# H_BRIGDE.net
KiCad netlist of a schematic drawn in Altium Designer
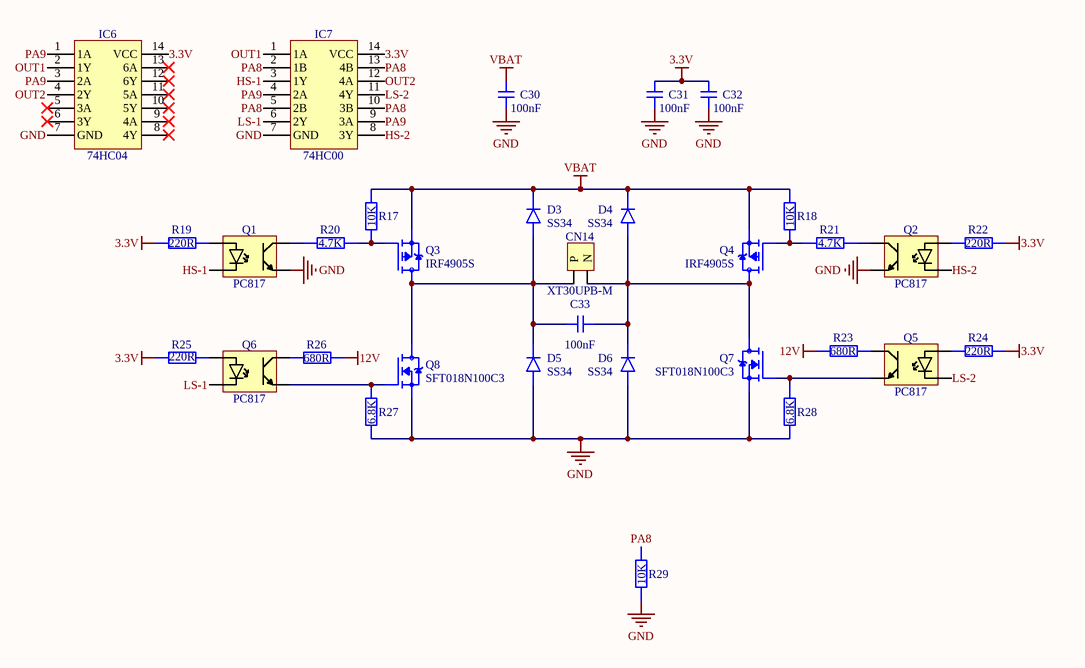
[diagram p0: H_BRIGDE.SchDoc]

(export (version "E")
  (design (tool "Eeschema 10.0.6"))
  (components
    (comp (ref "C30")
      (value "100nF")
      (footprint "CAP-0603-2")
      (description "100nF ±10% 50V Ceramic Capacitor X7R 0603")
      (fields (field (name "MANUFACTURER") "Samsung Electro-Mechanics") (field (name "LCSC PART #") "C1591"))
      (libsource (lib "CbyP") (part "CL10B104KB8NNNC"))
    )
    (comp (ref "C31")
      (value "100nF")
      (footprint "CAP-0603-2")
      (description "100nF ±10% 50V Ceramic Capacitor X7R 0603")
      (fields (field (name "MANUFACTURER") "Samsung Electro-Mechanics") (field (name "LCSC PART #") "C1591"))
      (libsource (lib "CbyP") (part "CL10B104KB8NNNC"))
    )
    (comp (ref "C32")
      (value "100nF")
      (footprint "CAP-0603-2")
      (description "100nF ±10% 50V Ceramic Capacitor X7R 0603")
      (fields (field (name "MANUFACTURER") "Samsung Electro-Mechanics") (field (name "LCSC PART #") "C1591"))
      (libsource (lib "CbyP") (part "CL10B104KB8NNNC"))
    )
    (comp (ref "C33")
      (value "100nF")
      (footprint "CAP-0603-2")
      (description "100nF ±10% 50V Ceramic Capacitor X7R 0603")
      (fields (field (name "MANUFACTURER") "Samsung Electro-Mechanics") (field (name "LCSC PART #") "C1591"))
      (libsource (lib "CbyP") (part "CL10B104KB8NNNC"))
    )
    (comp (ref "CN14")
      (value "XT30UPB-M")
      (footprint "XT30UPB-M")
      (description "Banana and Tip Connector Adapters")
      (fields
        (field (name "MANUFACTURER") "Changzhou Amass Elec")
        (field (name "MFR.PART #") "XT30PW-M30.G.Y")
      )
      (libsource (lib "CbyP") (part "XT30UPB-M"))
    )
    (comp (ref "D3")
      (value "SS34")
      (footprint "SMA(DO-214AC)")
      (description "Diode Independent 40V 3A Surface Mount SMA(DO-214AC)")
      (fields (field (name "MANUFACTURER") "GOODWORK") (field (name "LCSC PART #") "C908680"))
      (libsource (lib "CbyP") (part "SS34"))
    )
    (comp (ref "D4")
      (value "SS34")
      (footprint "SMA(DO-214AC)")
      (description "Diode Independent 40V 3A Surface Mount SMA(DO-214AC)")
      (fields (field (name "MANUFACTURER") "GOODWORK") (field (name "LCSC PART #") "C908680"))
      (libsource (lib "CbyP") (part "SS34"))
    )
    (comp (ref "D5")
      (value "SS34")
      (footprint "SMA(DO-214AC)")
      (description "Diode Independent 40V 3A Surface Mount SMA(DO-214AC)")
      (fields (field (name "MANUFACTURER") "GOODWORK") (field (name "LCSC PART #") "C908680"))
      (libsource (lib "CbyP") (part "SS34"))
    )
    (comp (ref "D6")
      (value "SS34")
      (footprint "SMA(DO-214AC)")
      (description "Diode Independent 40V 3A Surface Mount SMA(DO-214AC)")
      (fields (field (name "MANUFACTURER") "GOODWORK") (field (name "LCSC PART #") "C908680"))
      (libsource (lib "CbyP") (part "SS34"))
    )
    (comp (ref "IC6")
      (value "74HC04")
      (footprint "SOP-14")
      (description "2V~6V 16ns@6V,50pF 2uA 6 1 SOIC-14 Gates and Inverters RoHS")
      (fields (field (name "MANUFACTURER") "TI") (field (name "MFR.PART #") "SN74HC04DR"))
      (libsource (lib "CbyP") (part "SN74HC04DR"))
    )
    (comp (ref "IC7")
      (value "74HC00")
      (footprint "SOP-14")
      (description "2uA 2V~6V 15ns@6V,50pF SOIC-14 Gates and Inverters RoHS")
      (fields (field (name "MANUFACTURER") "TI") (field (name "MFR.PART #") "SN74HC00DR"))
      (libsource (lib "CbyP") (part "SN74HC00DR"))
    )
    (comp (ref "Q1")
      (value "PC817")
      (footprint "SOP-4")
      (description "Phototransistor Output 5kVrms 1 Channel SOP-4-2.54mm")
      (fields (field (name "MANUFACTURER") "UMW") (field (name "MFR.PART #") "PC817C-S"))
      (libsource (lib "CbyP") (part "PC817C-S"))
    )
    (comp (ref "Q2")
      (value "PC817")
      (footprint "SOP-4")
      (description "Phototransistor Output 5kVrms 1 Channel SOP-4-2.54mm")
      (fields (field (name "MANUFACTURER") "UMW") (field (name "MFR.PART #") "PC817C-S"))
      (libsource (lib "") (part "PC817C-S_1"))
    )
    (comp (ref "Q3")
      (value "IRF4905S")
      (footprint "TO-263")
      (description "P-Channel 55V 70A 170W Surface Mount D2PAK")
      (fields (field (name "MANUFACTURER") "Infineon") (field (name "MFR.PART #") "IRF4905STRLPBF"))
      (libsource (lib "CbyP") (part "IRF4905STRLPBF"))
    )
    (comp (ref "Q4")
      (value "IRF4905S")
      (footprint "TO-263")
      (description "P-Channel 55V 70A 170W Surface Mount D2PAK")
      (fields (field (name "MANUFACTURER") "Infineon") (field (name "MFR.PART #") "IRF4905STRLPBF"))
      (libsource (lib "CbyP") (part "IRF4905STRLPBF"))
    )
    (comp (ref "Q5")
      (value "PC817")
      (footprint "SOP-4")
      (description "Phototransistor Output 5kVrms 1 Channel SOP-4-2.54mm")
      (fields (field (name "MANUFACTURER") "UMW") (field (name "MFR.PART #") "PC817C-S"))
      (libsource (lib "") (part "PC817C-S_1"))
    )
    (comp (ref "Q6")
      (value "PC817")
      (footprint "SOP-4")
      (description "Phototransistor Output 5kVrms 1 Channel SOP-4-2.54mm")
      (fields (field (name "MANUFACTURER") "UMW") (field (name "MFR.PART #") "PC817C-S"))
      (libsource (lib "CbyP") (part "PC817C-S"))
    )
    (comp (ref "Q7")
      (value "SFT018N100C3")
      (footprint "TOLL")
      (description "N-Channel 100V 320A 312W Surface Mount TOLL")
      (fields (field (name "MANUFACTURER") "SCILICON") (field (name "LCSC PART #") "C42395330"))
      (libsource (lib "CbyP") (part "SFT018N100C3"))
    )
    (comp (ref "Q8")
      (value "SFT018N100C3")
      (footprint "TOLL")
      (description "N-Channel 100V 320A 312W Surface Mount TOLL")
      (fields (field (name "MANUFACTURER") "SCILICON") (field (name "LCSC PART #") "C42395330"))
      (libsource (lib "CbyP") (part "SFT018N100C3"))
    )
    (comp (ref "R17")
      (value "10K")
      (footprint "RES-0603-1")
      (description "100mW 10kΩ 75V Thick Film Resistor ±100ppm/℃ ±1% 0603 Chip Resistor - Surface Mount RoHS")
      (fields (field (name "MANUFACTURER") "YAGEO") (field (name "LCSC PART #") "C98220"))
      (libsource (lib "CbyP") (part "RC0603FR-0710KL"))
    )
    (comp (ref "R18")
      (value "10K")
      (footprint "RES-0603-1")
      (description "100mW 10kΩ 75V Thick Film Resistor ±100ppm/℃ ±1% 0603 Chip Resistor - Surface Mount RoHS")
      (fields (field (name "MANUFACTURER") "YAGEO") (field (name "LCSC PART #") "C98220"))
      (libsource (lib "CbyP") (part "RC0603FR-0710KL"))
    )
    (comp (ref "R19")
      (value "220R")
      (footprint "RES-0603-1")
      (description "220Ω ±1% 100mW 0603 Thick Film Resistor")
      (fields (field (name "MANUFACTURER") "UNI-ROYAL") (field (name "MFR.PART #") "0603WAF2200T5E"))
      (libsource (lib "CbyP") (part "0603WAF2200T5E"))
    )
    (comp (ref "R20")
      (value "4.7K")
      (footprint "RES-0603-1")
      (description "100mW 4.7kΩ 75V Thick Film Resistor ±100ppm/℃ ±1% 0603 Chip Resistor - Surface Mount RoHS")
      (fields (field (name "MANUFACTURER") "YAGEO") (field (name "MFR.PART #") "RC0603FR-074K7L"))
      (libsource (lib "CbyP") (part "RC0603FR-074K7L"))
    )
    (comp (ref "R21")
      (value "4.7K")
      (footprint "RES-0603-1")
      (description "100mW 4.7kΩ 75V Thick Film Resistor ±100ppm/℃ ±1% 0603 Chip Resistor - Surface Mount RoHS")
      (fields (field (name "MANUFACTURER") "YAGEO") (field (name "MFR.PART #") "RC0603FR-074K7L"))
      (libsource (lib "CbyP") (part "RC0603FR-074K7L"))
    )
    (comp (ref "R22")
      (value "220R")
      (footprint "RES-0603-1")
      (description "220Ω ±1% 100mW 0603 Thick Film Resistor")
      (fields (field (name "MANUFACTURER") "UNI-ROYAL") (field (name "MFR.PART #") "0603WAF2200T5E"))
      (libsource (lib "CbyP") (part "0603WAF2200T5E"))
    )
    (comp (ref "R23")
      (value "680R")
      (footprint "RES-0603-1")
      (description "680Ω ±1% 100mW 0603 Thick Film Resistor")
      (fields (field (name "MANUFACTURER") "FOJAN") (field (name "MFR.PART #") "FRC0603F6800TS"))
      (libsource (lib "CbyP") (part "FRC0603F6800TS"))
    )
    (comp (ref "R24")
      (value "220R")
      (footprint "RES-0603-1")
      (description "220Ω ±1% 100mW 0603 Thick Film Resistor")
      (fields (field (name "MANUFACTURER") "UNI-ROYAL") (field (name "MFR.PART #") "0603WAF2200T5E"))
      (libsource (lib "CbyP") (part "0603WAF2200T5E"))
    )
    (comp (ref "R25")
      (value "220R")
      (footprint "RES-0603-1")
      (description "220Ω ±1% 100mW 0603 Thick Film Resistor")
      (fields (field (name "MANUFACTURER") "UNI-ROYAL") (field (name "MFR.PART #") "0603WAF2200T5E"))
      (libsource (lib "CbyP") (part "0603WAF2200T5E"))
    )
    (comp (ref "R26")
      (value "680R")
      (footprint "RES-0603-1")
      (description "680Ω ±1% 100mW 0603 Thick Film Resistor")
      (fields (field (name "MANUFACTURER") "FOJAN") (field (name "MFR.PART #") "FRC0603F6800TS"))
      (libsource (lib "CbyP") (part "FRC0603F6800TS"))
    )
    (comp (ref "R27")
      (value "6.8K")
      (footprint "RES-0603-1")
      (description "6.8kΩ ±1% 100mW 0603 Thick Film Resistor")
      (fields (field (name "MANUFACTURER") "UNI-ROYAL") (field (name "MFR.PART #") "0603WAF6801T5E"))
      (libsource (lib "CbyP") (part "0603WAF6801T5E"))
    )
    (comp (ref "R28")
      (value "6.8K")
      (footprint "RES-0603-1")
      (description "6.8kΩ ±1% 100mW 0603 Thick Film Resistor")
      (fields (field (name "MANUFACTURER") "UNI-ROYAL") (field (name "MFR.PART #") "0603WAF6801T5E"))
      (libsource (lib "CbyP") (part "0603WAF6801T5E"))
    )
    (comp (ref "R29")
      (value "10K")
      (footprint "RES-0603-1")
      (description "100mW 10kΩ 75V Thick Film Resistor ±100ppm/℃ ±1% 0603 Chip Resistor - Surface Mount RoHS")
      (fields (field (name "MANUFACTURER") "YAGEO") (field (name "LCSC PART #") "C98220"))
      (libsource (lib "CbyP") (part "RC0603FR-0710KL"))
    )
  )
  (nets
    (net (code "1") (name "/HS-1") (class "Default")
      (node (ref "IC7") (pin "3") (pinfunction "1Y_3") (pintype "passive"))
      (node (ref "Q1") (pin "2") (pinfunction "K_2") (pintype "passive"))
    )
    (net (code "2") (name "/HS-2") (class "Default")
      (node (ref "IC7") (pin "8") (pinfunction "3Y_8") (pintype "passive"))
      (node (ref "Q2") (pin "2") (pinfunction "K_2") (pintype "passive"))
    )
    (net (code "3") (name "/LS-1") (class "Default")
      (node (ref "IC7") (pin "6") (pinfunction "2Y_6") (pintype "passive"))
      (node (ref "Q6") (pin "2") (pinfunction "K_2") (pintype "passive"))
    )
    (net (code "4") (name "/LS-2") (class "Default")
      (node (ref "IC7") (pin "11") (pinfunction "4Y_11") (pintype "passive"))
      (node (ref "Q5") (pin "2") (pinfunction "K_2") (pintype "passive"))
    )
    (net (code "5") (name "/OUT1") (class "Default")
      (node (ref "IC6") (pin "2") (pinfunction "1Y_2") (pintype "passive"))
      (node (ref "IC7") (pin "1") (pinfunction "1A_1") (pintype "passive"))
    )
    (net (code "6") (name "/OUT2") (class "Default")
      (node (ref "IC6") (pin "4") (pinfunction "2Y_4") (pintype "passive"))
      (node (ref "IC7") (pin "12") (pinfunction "4A_12") (pintype "passive"))
    )
    (net (code "7") (name "/PA8") (class "Default")
      (node (ref "IC7") (pin "10") (pinfunction "3B_10") (pintype "passive"))
      (node (ref "IC7") (pin "13") (pinfunction "4B_13") (pintype "passive"))
      (node (ref "IC7") (pin "2") (pinfunction "1B_2") (pintype "passive"))
      (node (ref "IC7") (pin "5") (pinfunction "2B_5") (pintype "passive"))
      (node (ref "R29") (pin "2") (pinfunction "2_2") (pintype "passive"))
    )
    (net (code "8") (name "/PA9") (class "Default")
      (node (ref "IC6") (pin "1") (pinfunction "1A_1") (pintype "passive"))
      (node (ref "IC6") (pin "3") (pinfunction "2A_3") (pintype "passive"))
      (node (ref "IC7") (pin "4") (pinfunction "2A_4") (pintype "passive"))
      (node (ref "IC7") (pin "9") (pinfunction "3A_9") (pintype "passive"))
    )
    (net (code "9") (name "3.3V") (class "Default")
      (node (ref "C31") (pin "1") (pinfunction "1_1") (pintype "passive"))
      (node (ref "C32") (pin "1") (pinfunction "1_1") (pintype "passive"))
      (node (ref "IC6") (pin "14") (pinfunction "VCC_14") (pintype "passive"))
      (node (ref "IC7") (pin "14") (pinfunction "VCC_14") (pintype "passive"))
      (node (ref "R19") (pin "2") (pinfunction "2_2") (pintype "passive"))
      (node (ref "R22") (pin "1") (pinfunction "1_1") (pintype "passive"))
      (node (ref "R24") (pin "1") (pinfunction "1_1") (pintype "passive"))
      (node (ref "R25") (pin "2") (pinfunction "2_2") (pintype "passive"))
    )
    (net (code "10") (name "12V") (class "Default")
      (node (ref "R23") (pin "2") (pinfunction "2_2") (pintype "passive"))
      (node (ref "R26") (pin "2") (pinfunction "2_2") (pintype "passive"))
    )
    (net (code "11") (name "GND") (class "Default")
      (node (ref "C30") (pin "2") (pinfunction "2_2") (pintype "passive"))
      (node (ref "C31") (pin "2") (pinfunction "2_2") (pintype "passive"))
      (node (ref "C32") (pin "2") (pinfunction "2_2") (pintype "passive"))
      (node (ref "D5") (pin "1") (pinfunction "A_1") (pintype "passive"))
      (node (ref "D6") (pin "1") (pinfunction "A_1") (pintype "passive"))
      (node (ref "IC6") (pin "7") (pinfunction "GND_7") (pintype "passive"))
      (node (ref "IC7") (pin "7") (pinfunction "GND_7") (pintype "passive"))
      (node (ref "Q1") (pin "3") (pinfunction "E_3") (pintype "passive"))
      (node (ref "Q2") (pin "3") (pinfunction "E_3") (pintype "passive"))
      (node (ref "Q7") (pin "2") (pinfunction "S_2") (pintype "passive"))
      (node (ref "Q8") (pin "2") (pinfunction "S_2") (pintype "passive"))
      (node (ref "R27") (pin "1") (pinfunction "1_1") (pintype "passive"))
      (node (ref "R28") (pin "1") (pinfunction "1_1") (pintype "passive"))
      (node (ref "R29") (pin "1") (pinfunction "1_1") (pintype "passive"))
    )
    (net (code "12") (name "Net-(CN14-N)") (class "Default")
      (node (ref "C33") (pin "1") (pinfunction "1_1") (pintype "passive"))
      (node (ref "CN14") (pin "2") (pinfunction "N_2") (pintype "passive"))
      (node (ref "D4") (pin "1") (pinfunction "A_1") (pintype "passive"))
      (node (ref "D6") (pin "2") (pinfunction "K_2") (pintype "passive"))
      (node (ref "Q4") (pin "2") (pinfunction "D_2") (pintype "passive"))
      (node (ref "Q7") (pin "3") (pinfunction "D_3") (pintype "passive"))
    )
    (net (code "13") (name "Net-(CN14-P)") (class "Default")
      (node (ref "C33") (pin "2") (pinfunction "2_2") (pintype "passive"))
      (node (ref "CN14") (pin "1") (pinfunction "P_1") (pintype "passive"))
      (node (ref "D3") (pin "1") (pinfunction "A_1") (pintype "passive"))
      (node (ref "D5") (pin "2") (pinfunction "K_2") (pintype "passive"))
      (node (ref "Q3") (pin "2") (pinfunction "D_2") (pintype "passive"))
      (node (ref "Q8") (pin "3") (pinfunction "D_3") (pintype "passive"))
    )
    (net (code "14") (name "Net-(Q1-A)") (class "Default")
      (node (ref "Q1") (pin "1") (pinfunction "A_1") (pintype "passive"))
      (node (ref "R19") (pin "1") (pinfunction "1_1") (pintype "passive"))
    )
    (net (code "15") (name "Net-(Q1-C)") (class "Default")
      (node (ref "Q1") (pin "4") (pinfunction "C_4") (pintype "passive"))
      (node (ref "R20") (pin "1") (pinfunction "1_1") (pintype "passive"))
    )
    (net (code "16") (name "Net-(Q2-A)") (class "Default")
      (node (ref "Q2") (pin "1") (pinfunction "A_1") (pintype "passive"))
      (node (ref "R22") (pin "2") (pinfunction "2_2") (pintype "passive"))
    )
    (net (code "17") (name "Net-(Q2-C)") (class "Default")
      (node (ref "Q2") (pin "4") (pinfunction "C_4") (pintype "passive"))
      (node (ref "R21") (pin "2") (pinfunction "2_2") (pintype "passive"))
    )
    (net (code "18") (name "Net-(Q3-G)") (class "Default")
      (node (ref "Q3") (pin "1") (pinfunction "G_1") (pintype "passive"))
      (node (ref "R17") (pin "1") (pinfunction "1_1") (pintype "passive"))
      (node (ref "R20") (pin "2") (pinfunction "2_2") (pintype "passive"))
    )
    (net (code "19") (name "Net-(Q4-G)") (class "Default")
      (node (ref "Q4") (pin "1") (pinfunction "G_1") (pintype "passive"))
      (node (ref "R18") (pin "1") (pinfunction "1_1") (pintype "passive"))
      (node (ref "R21") (pin "1") (pinfunction "1_1") (pintype "passive"))
    )
    (net (code "20") (name "Net-(Q5-A)") (class "Default")
      (node (ref "Q5") (pin "1") (pinfunction "A_1") (pintype "passive"))
      (node (ref "R24") (pin "2") (pinfunction "2_2") (pintype "passive"))
    )
    (net (code "21") (name "Net-(Q5-C)") (class "Default")
      (node (ref "Q5") (pin "4") (pinfunction "C_4") (pintype "passive"))
      (node (ref "R23") (pin "1") (pinfunction "1_1") (pintype "passive"))
    )
    (net (code "22") (name "Net-(Q5-E)") (class "Default")
      (node (ref "Q5") (pin "3") (pinfunction "E_3") (pintype "passive"))
      (node (ref "Q7") (pin "1") (pinfunction "G_1") (pintype "passive"))
      (node (ref "R28") (pin "2") (pinfunction "2_2") (pintype "passive"))
    )
    (net (code "23") (name "Net-(Q6-A)") (class "Default")
      (node (ref "Q6") (pin "1") (pinfunction "A_1") (pintype "passive"))
      (node (ref "R25") (pin "1") (pinfunction "1_1") (pintype "passive"))
    )
    (net (code "24") (name "Net-(Q6-C)") (class "Default")
      (node (ref "Q6") (pin "4") (pinfunction "C_4") (pintype "passive"))
      (node (ref "R26") (pin "1") (pinfunction "1_1") (pintype "passive"))
    )
    (net (code "25") (name "Net-(Q6-E)") (class "Default")
      (node (ref "Q6") (pin "3") (pinfunction "E_3") (pintype "passive"))
      (node (ref "Q8") (pin "1") (pinfunction "G_1") (pintype "passive"))
      (node (ref "R27") (pin "2") (pinfunction "2_2") (pintype "passive"))
    )
    (net (code "26") (name "VBAT") (class "Default")
      (node (ref "C30") (pin "1") (pinfunction "1_1") (pintype "passive"))
      (node (ref "D3") (pin "2") (pinfunction "K_2") (pintype "passive"))
      (node (ref "D4") (pin "2") (pinfunction "K_2") (pintype "passive"))
      (node (ref "Q3") (pin "3") (pinfunction "S_3") (pintype "passive"))
      (node (ref "Q4") (pin "3") (pinfunction "S_3") (pintype "passive"))
      (node (ref "R17") (pin "2") (pinfunction "2_2") (pintype "passive"))
      (node (ref "R18") (pin "2") (pinfunction "2_2") (pintype "passive"))
    )
    (net (code "27") (name "unconnected-(IC6-3A-Pad5)") (class "Default")
      (node (ref "IC6") (pin "5") (pinfunction "3A_5") (pintype "passive+no_connect"))
    )
    (net (code "28") (name "unconnected-(IC6-3Y-Pad6)") (class "Default")
      (node (ref "IC6") (pin "6") (pinfunction "3Y_6") (pintype "passive+no_connect"))
    )
    (net (code "29") (name "unconnected-(IC6-4A-Pad9)") (class "Default")
      (node (ref "IC6") (pin "9") (pinfunction "4A_9") (pintype "passive+no_connect"))
    )
    (net (code "30") (name "unconnected-(IC6-4Y-Pad8)") (class "Default")
      (node (ref "IC6") (pin "8") (pinfunction "4Y_8") (pintype "passive+no_connect"))
    )
    (net (code "31") (name "unconnected-(IC6-5A-Pad11)") (class "Default")
      (node (ref "IC6") (pin "11") (pinfunction "5A_11") (pintype "passive+no_connect"))
    )
    (net (code "32") (name "unconnected-(IC6-5Y-Pad10)") (class "Default")
      (node (ref "IC6") (pin "10") (pinfunction "5Y_10") (pintype "passive+no_connect"))
    )
    (net (code "33") (name "unconnected-(IC6-6A-Pad13)") (class "Default")
      (node (ref "IC6") (pin "13") (pinfunction "6A_13") (pintype "passive+no_connect"))
    )
    (net (code "34") (name "unconnected-(IC6-6Y-Pad12)") (class "Default")
      (node (ref "IC6") (pin "12") (pinfunction "6Y_12") (pintype "passive+no_connect"))
    )
  )
)
